# SCH_Pathfinder-V1_2025-10-27.net
KiCad netlist of a schematic drawn in EasyEDA
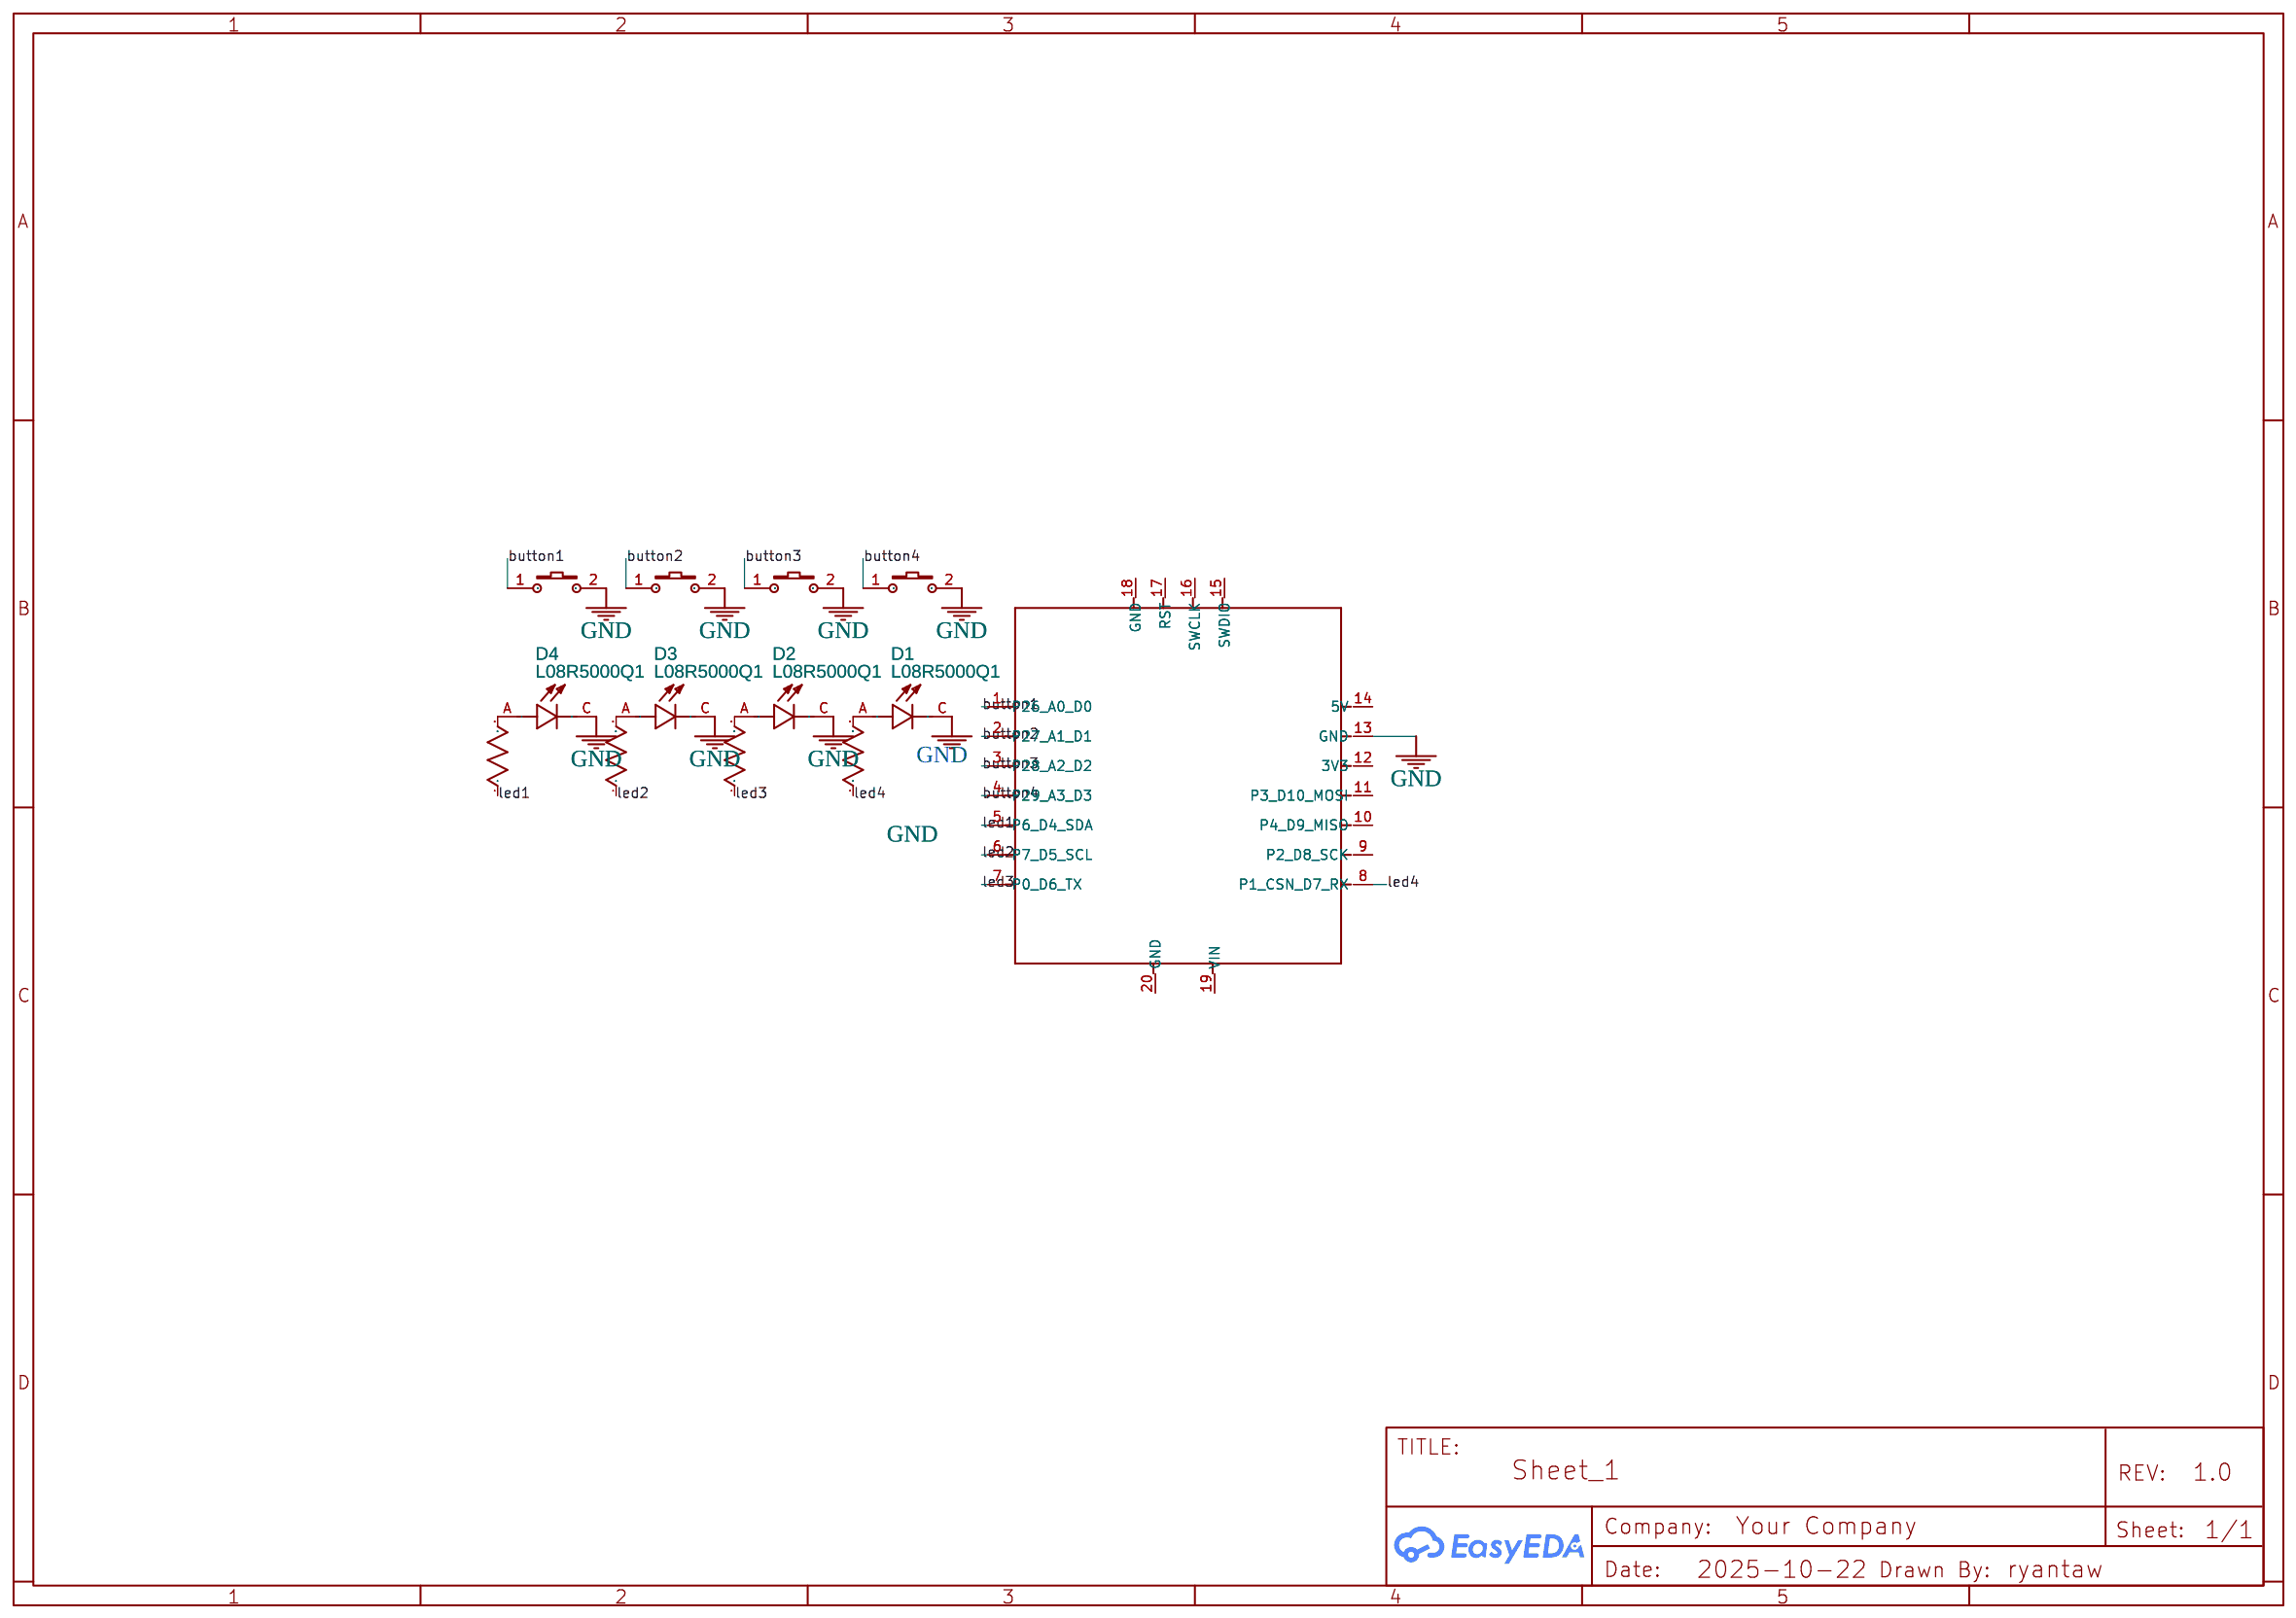
[diagram p0: schematic sheet]

(export (version "E")
  (design (tool "Eeschema 10.0.6"))
  (components
    (comp (ref "D1") (value "L08R5000Q1") (libsource (lib "") (part "L08R5000Q1")))
    (comp (ref "D2") (value "L08R5000Q1") (libsource (lib "") (part "L08R5000Q1")))
    (comp (ref "D3") (value "L08R5000Q1") (libsource (lib "") (part "L08R5000Q1")))
    (comp (ref "D4") (value "L08R5000Q1") (libsource (lib "") (part "L08R5000Q1")))
    (comp (ref "KEY1")
      (value "K2-3.6×6.1_SMD")
      (fields (field (name "Manufacturer Part") "K2-1107ST-A4SW-06"))
      (libsource (lib "") (part "K2-3.6×6.1_SMD"))
    )
    (comp (ref "KEY2")
      (value "K2-3.6×6.1_SMD")
      (fields (field (name "Manufacturer Part") "K2-1107ST-A4SW-06"))
      (libsource (lib "") (part "K2-3.6×6.1_SMD"))
    )
    (comp (ref "KEY3")
      (value "K2-3.6×6.1_SMD")
      (fields (field (name "Manufacturer Part") "K2-1107ST-A4SW-06"))
      (libsource (lib "") (part "K2-3.6×6.1_SMD"))
    )
    (comp (ref "KEY4")
      (value "K2-3.6×6.1_SMD")
      (fields (field (name "Manufacturer Part") "K2-1107ST-A4SW-06"))
      (libsource (lib "") (part "K2-3.6×6.1_SMD"))
    )
    (comp (ref "R1") (value "1k") (libsource (lib "") (part "R_0603_US")))
    (comp (ref "R2") (value "1k") (libsource (lib "") (part "R_0603_US")))
    (comp (ref "R3") (value "1k") (libsource (lib "") (part "R_0603_US")))
    (comp (ref "R4") (value "1k") (libsource (lib "") (part "R_0603_US")))
    (comp (ref "U1") (value "XIAO-RP2040") (libsource (lib "") (part "XIAO-RP2040")))
  )
  (nets
    (net (code "1") (name "/button1") (class "Default")
      (node (ref "KEY1") (pin "1") (pinfunction "1_1") (pintype "unspecified"))
      (node (ref "U1") (pin "1") (pinfunction "P26_A0_D0_1") (pintype "bidirectional"))
    )
    (net (code "2") (name "/button2") (class "Default")
      (node (ref "KEY2") (pin "1") (pinfunction "1_1") (pintype "unspecified"))
      (node (ref "U1") (pin "2") (pinfunction "P27_A1_D1_2") (pintype "bidirectional"))
    )
    (net (code "3") (name "/button3") (class "Default")
      (node (ref "KEY3") (pin "1") (pinfunction "1_1") (pintype "unspecified"))
      (node (ref "U1") (pin "3") (pinfunction "P28_A2_D2_3") (pintype "bidirectional"))
    )
    (net (code "4") (name "/button4") (class "Default")
      (node (ref "KEY4") (pin "1") (pinfunction "1_1") (pintype "unspecified"))
      (node (ref "U1") (pin "4") (pinfunction "P29_A3_D3_4") (pintype "bidirectional"))
    )
    (net (code "5") (name "/led1") (class "Default")
      (node (ref "R1") (pin "1") (pinfunction "1_1") (pintype "unspecified"))
      (node (ref "U1") (pin "5") (pinfunction "P6_D4_SDA_5") (pintype "bidirectional"))
    )
    (net (code "6") (name "/led2") (class "Default")
      (node (ref "R2") (pin "1") (pinfunction "1_1") (pintype "unspecified"))
      (node (ref "U1") (pin "6") (pinfunction "P7_D5_SCL_6") (pintype "bidirectional"))
    )
    (net (code "7") (name "/led3") (class "Default")
      (node (ref "R3") (pin "1") (pinfunction "1_1") (pintype "unspecified"))
      (node (ref "U1") (pin "7") (pinfunction "P0_D6_TX_7") (pintype "bidirectional"))
    )
    (net (code "8") (name "/led4") (class "Default")
      (node (ref "R4") (pin "1") (pinfunction "1_1") (pintype "unspecified"))
      (node (ref "U1") (pin "8") (pinfunction "P1_CSN_D7_RX_8") (pintype "bidirectional"))
    )
    (net (code "9") (name "GND") (class "Default")
      (node (ref "D1") (pin "C") (pinfunction "C_C") (pintype "bidirectional"))
      (node (ref "D2") (pin "C") (pinfunction "C_C") (pintype "bidirectional"))
      (node (ref "D3") (pin "C") (pinfunction "C_C") (pintype "bidirectional"))
      (node (ref "D4") (pin "C") (pinfunction "C_C") (pintype "bidirectional"))
      (node (ref "KEY1") (pin "2") (pinfunction "2_2") (pintype "unspecified"))
      (node (ref "KEY2") (pin "2") (pinfunction "2_2") (pintype "unspecified"))
      (node (ref "KEY3") (pin "2") (pinfunction "2_2") (pintype "unspecified"))
      (node (ref "KEY4") (pin "2") (pinfunction "2_2") (pintype "unspecified"))
      (node (ref "U1") (pin "13") (pinfunction "GND_13") (pintype "bidirectional"))
    )
    (net (code "10") (name "Net-(D1-PadA)") (class "Default")
      (node (ref "D1") (pin "A") (pinfunction "A_A") (pintype "bidirectional"))
      (node (ref "R4") (pin "2") (pinfunction "2_2") (pintype "unspecified"))
    )
    (net (code "11") (name "Net-(D2-PadA)") (class "Default")
      (node (ref "D2") (pin "A") (pinfunction "A_A") (pintype "bidirectional"))
      (node (ref "R3") (pin "2") (pinfunction "2_2") (pintype "unspecified"))
    )
    (net (code "12") (name "Net-(D3-PadA)") (class "Default")
      (node (ref "D3") (pin "A") (pinfunction "A_A") (pintype "bidirectional"))
      (node (ref "R2") (pin "2") (pinfunction "2_2") (pintype "unspecified"))
    )
    (net (code "13") (name "Net-(D4-PadA)") (class "Default")
      (node (ref "D4") (pin "A") (pinfunction "A_A") (pintype "bidirectional"))
      (node (ref "R1") (pin "2") (pinfunction "2_2") (pintype "unspecified"))
    )
    (net (code "14") (name "unconnected-(U1-3V3-Pad12)") (class "Default")
      (node (ref "U1") (pin "12") (pinfunction "3V3_12") (pintype "bidirectional"))
    )
    (net (code "15") (name "unconnected-(U1-5V-Pad14)") (class "Default")
      (node (ref "U1") (pin "14") (pinfunction "5V_14") (pintype "bidirectional"))
    )
    (net (code "16") (name "unconnected-(U1-GND-Pad18)") (class "Default")
      (node (ref "U1") (pin "18") (pinfunction "GND_18") (pintype "bidirectional"))
    )
    (net (code "17") (name "unconnected-(U1-GND-Pad20)") (class "Default")
      (node (ref "U1") (pin "20") (pinfunction "GND_20") (pintype "bidirectional"))
    )
    (net (code "18") (name "unconnected-(U1-P2_D8_SCK-Pad9)") (class "Default")
      (node (ref "U1") (pin "9") (pinfunction "P2_D8_SCK_9") (pintype "bidirectional"))
    )
    (net (code "19") (name "unconnected-(U1-P3_D10_MOSI-Pad11)") (class "Default")
      (node (ref "U1") (pin "11") (pinfunction "P3_D10_MOSI_11") (pintype "bidirectional"))
    )
    (net (code "20") (name "unconnected-(U1-P4_D9_MISO-Pad10)") (class "Default")
      (node (ref "U1") (pin "10") (pinfunction "P4_D9_MISO_10") (pintype "bidirectional"))
    )
    (net (code "21") (name "unconnected-(U1-RST-Pad17)") (class "Default")
      (node (ref "U1") (pin "17") (pinfunction "RST_17") (pintype "bidirectional"))
    )
    (net (code "22") (name "unconnected-(U1-SWCLK-Pad16)") (class "Default")
      (node (ref "U1") (pin "16") (pinfunction "SWCLK_16") (pintype "bidirectional"))
    )
    (net (code "23") (name "unconnected-(U1-SWDIO-Pad15)") (class "Default")
      (node (ref "U1") (pin "15") (pinfunction "SWDIO_15") (pintype "bidirectional"))
    )
    (net (code "24") (name "unconnected-(U1-VIN-Pad19)") (class "Default")
      (node (ref "U1") (pin "19") (pinfunction "VIN_19") (pintype "bidirectional"))
    )
  )
)
